# compressor.net
KiCad netlist of a schematic drawn in EAGLE
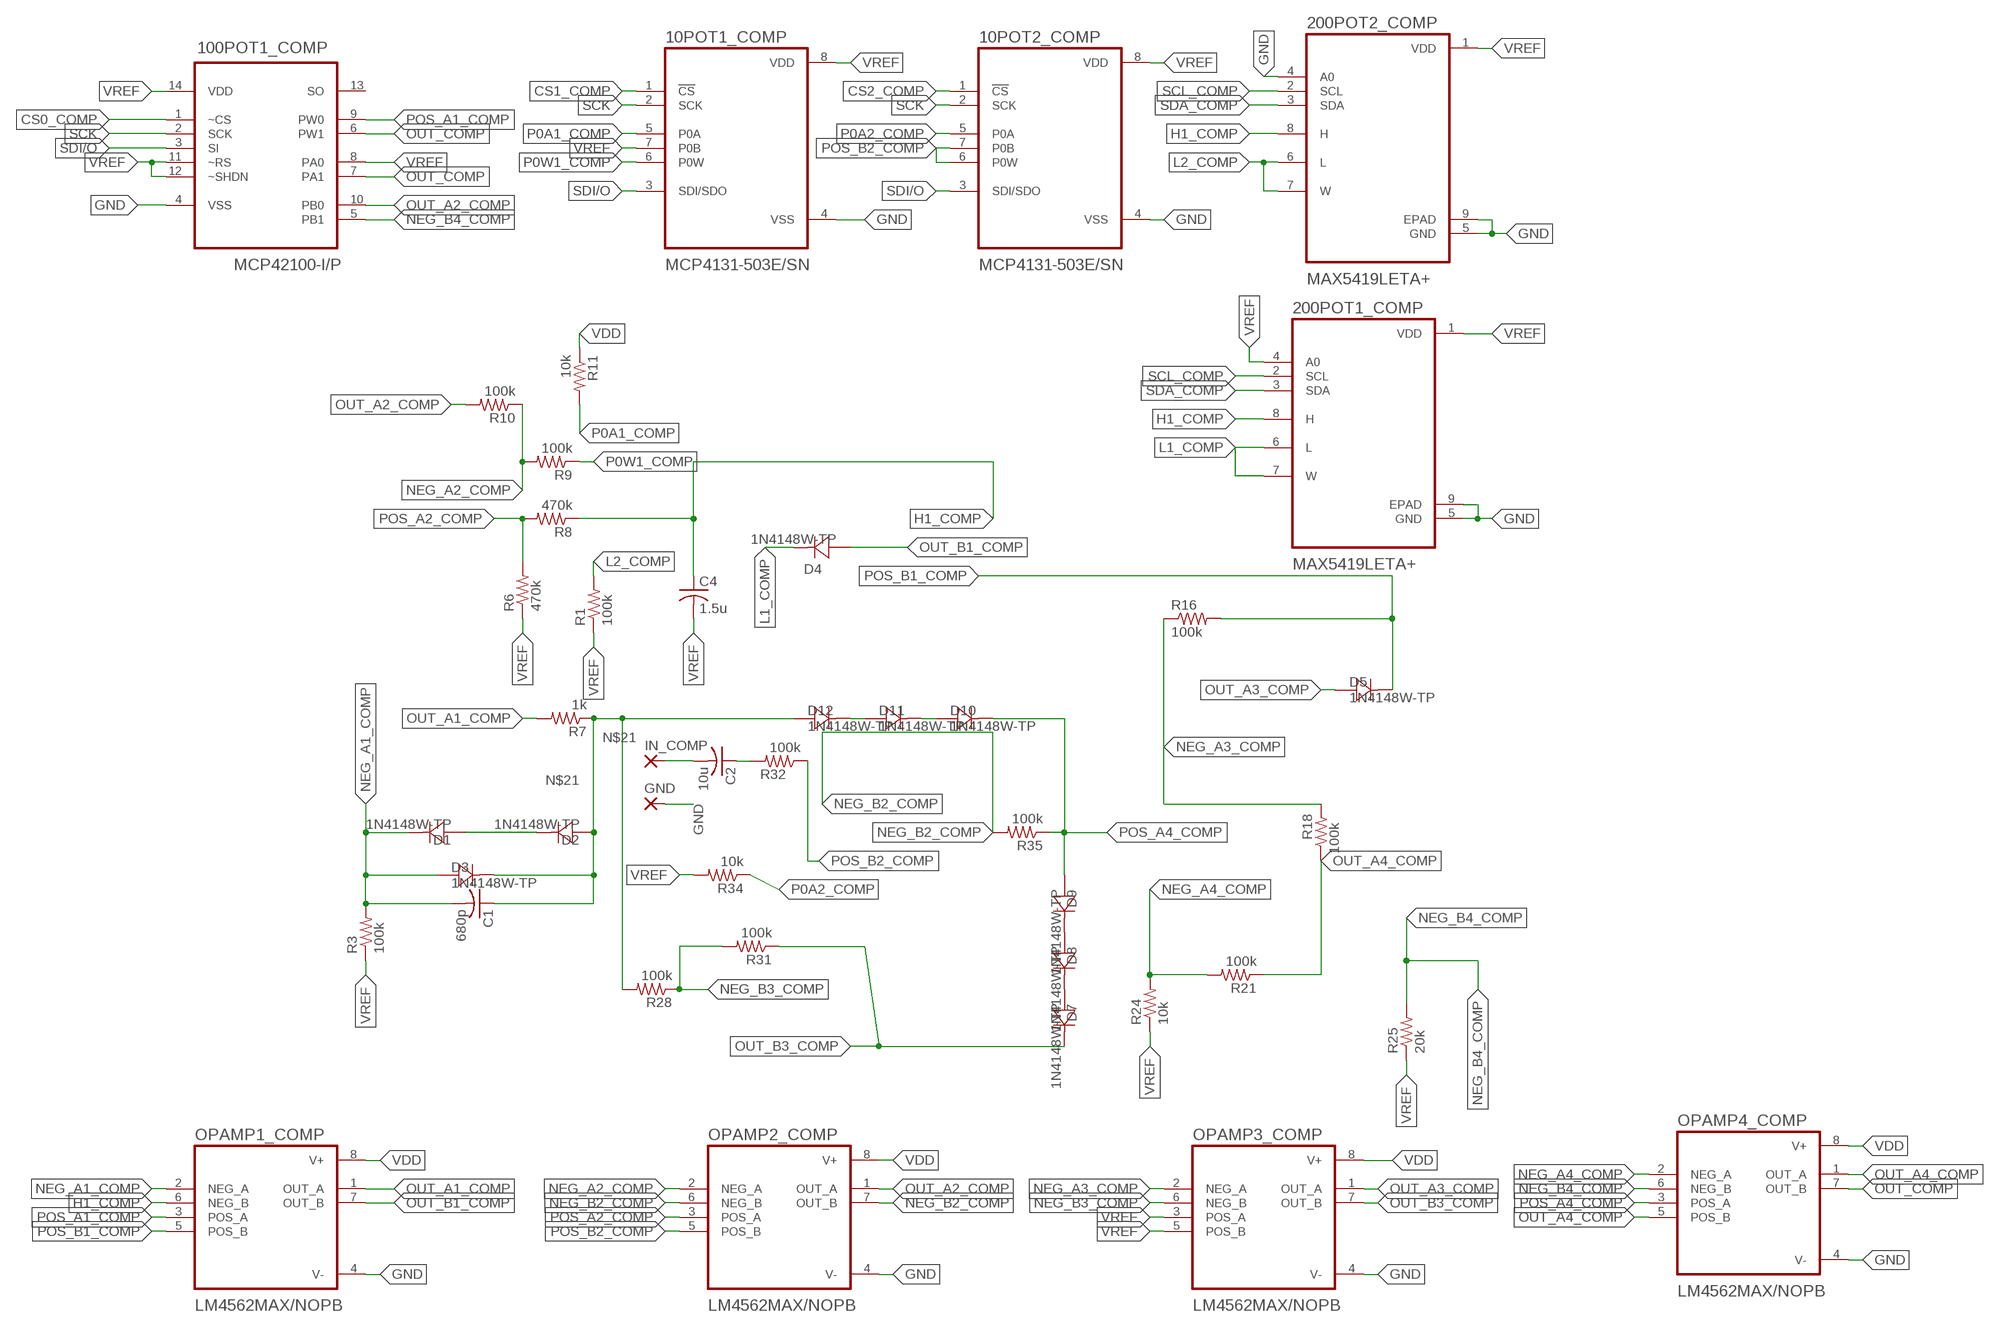
[diagram p0: schematic, sheet 1]

(export (version "E")
  (design (tool "Eeschema 10.0.6"))
  (components
    (comp (ref "10POT1_COMP")
      (value "MCP4131-503E/SN")
      (footprint "eagle-import:SOIC127P599X175-8N")
      (fields (field (name "MF") "Microchip"))
      (libsource (lib "eagle-import") (part "MCP4131-503E/SN"))
    )
    (comp (ref "10POT2_COMP")
      (value "MCP4131-503E/SN")
      (footprint "eagle-import:SOIC127P599X175-8N")
      (fields (field (name "MF") "Microchip"))
      (libsource (lib "eagle-import") (part "MCP4131-503E/SN"))
    )
    (comp (ref "100POT1_COMP")
      (value "MCP42100-I/P")
      (footprint "eagle-import:DIP254P762X432-14")
      (fields (field (name "MF") "Microchip"))
      (libsource (lib "eagle-import") (part "MCP42100-I/P"))
    )
    (comp (ref "200POT1_COMP")
      (value "MAX5419LETA+")
      (footprint "eagle-import:SON65P300X300X80-9N")
      (fields (field (name "MF") "Analog Devices"))
      (libsource (lib "eagle-import") (part "MAX5419LETA+"))
    )
    (comp (ref "200POT2_COMP")
      (value "MAX5419LETA+")
      (footprint "eagle-import:SON65P300X300X80-9N")
      (fields (field (name "MF") "Analog Devices"))
      (libsource (lib "eagle-import") (part "MAX5419LETA+"))
    )
    (comp (ref "C1")
      (value "680p")
      (footprint "eagle-import:C0402")
      (libsource (lib "eagle-import") (part "C-USC0402"))
    )
    (comp (ref "C2")
      (value "10u")
      (footprint "eagle-import:C0402")
      (libsource (lib "eagle-import") (part "C-USC0402"))
    )
    (comp (ref "C4")
      (value "1.5u")
      (footprint "eagle-import:C0402")
      (libsource (lib "eagle-import") (part "C-USC0402"))
    )
    (comp (ref "D1")
      (value "1N4148W-TP")
      (footprint "eagle-import:SOD123")
      (fields (field (name "MF") "Micro Commercial"))
      (libsource (lib "eagle-import") (part "1N4148W-TP"))
    )
    (comp (ref "D2")
      (value "1N4148W-TP")
      (footprint "eagle-import:SOD123")
      (fields (field (name "MF") "Micro Commercial"))
      (libsource (lib "eagle-import") (part "1N4148W-TP"))
    )
    (comp (ref "D3")
      (value "1N4148W-TP")
      (footprint "eagle-import:SOD123")
      (fields (field (name "MF") "Micro Commercial"))
      (libsource (lib "eagle-import") (part "1N4148W-TP"))
    )
    (comp (ref "D4")
      (value "1N4148W-TP")
      (footprint "eagle-import:SOD123")
      (fields (field (name "MF") "Micro Commercial"))
      (libsource (lib "eagle-import") (part "1N4148W-TP"))
    )
    (comp (ref "D5")
      (value "1N4148W-TP")
      (footprint "eagle-import:SOD123")
      (fields (field (name "MF") "Micro Commercial"))
      (libsource (lib "eagle-import") (part "1N4148W-TP"))
    )
    (comp (ref "D7")
      (value "1N4148W-TP")
      (footprint "eagle-import:SOD123")
      (fields (field (name "MF") "Micro Commercial"))
      (libsource (lib "eagle-import") (part "1N4148W-TP"))
    )
    (comp (ref "D8")
      (value "1N4148W-TP")
      (footprint "eagle-import:SOD123")
      (fields (field (name "MF") "Micro Commercial"))
      (libsource (lib "eagle-import") (part "1N4148W-TP"))
    )
    (comp (ref "D9")
      (value "1N4148W-TP")
      (footprint "eagle-import:SOD123")
      (fields (field (name "MF") "Micro Commercial"))
      (libsource (lib "eagle-import") (part "1N4148W-TP"))
    )
    (comp (ref "D10")
      (value "1N4148W-TP")
      (footprint "eagle-import:SOD123")
      (fields (field (name "MF") "Micro Commercial"))
      (libsource (lib "eagle-import") (part "1N4148W-TP"))
    )
    (comp (ref "D11")
      (value "1N4148W-TP")
      (footprint "eagle-import:SOD123")
      (fields (field (name "MF") "Micro Commercial"))
      (libsource (lib "eagle-import") (part "1N4148W-TP"))
    )
    (comp (ref "D12")
      (value "1N4148W-TP")
      (footprint "eagle-import:SOD123")
      (fields (field (name "MF") "Micro Commercial"))
      (libsource (lib "eagle-import") (part "1N4148W-TP"))
    )
    (comp (ref "GND")
      (value "SMD5")
      (footprint "eagle-import:SMD2,54-5,08")
      (libsource (lib "eagle-import") (part "SMD5"))
    )
    (comp (ref "IN_COMP")
      (value "SMD5")
      (footprint "eagle-import:SMD2,54-5,08")
      (libsource (lib "eagle-import") (part "SMD5"))
    )
    (comp (ref "OPAMP1_COMP")
      (value "LM4562MAX/NOPB")
      (footprint "eagle-import:SOIC127P599X175-8N")
      (fields (field (name "MF") "Texas Instruments"))
      (libsource (lib "eagle-import") (part "LM4562MAX/NOPB"))
    )
    (comp (ref "OPAMP2_COMP")
      (value "LM4562MAX/NOPB")
      (footprint "eagle-import:SOIC127P599X175-8N")
      (fields (field (name "MF") "Texas Instruments"))
      (libsource (lib "eagle-import") (part "LM4562MAX/NOPB"))
    )
    (comp (ref "OPAMP3_COMP")
      (value "LM4562MAX/NOPB")
      (footprint "eagle-import:SOIC127P599X175-8N")
      (fields (field (name "MF") "Texas Instruments"))
      (libsource (lib "eagle-import") (part "LM4562MAX/NOPB"))
    )
    (comp (ref "OPAMP4_COMP")
      (value "LM4562MAX/NOPB")
      (footprint "eagle-import:SOIC127P599X175-8N")
      (fields (field (name "MF") "Texas Instruments"))
      (libsource (lib "eagle-import") (part "LM4562MAX/NOPB"))
    )
    (comp (ref "R1")
      (value "100k")
      (footprint "eagle-import:R0402")
      (libsource (lib "eagle-import") (part "R-US_R0402"))
    )
    (comp (ref "R3")
      (value "100k")
      (footprint "eagle-import:R0402")
      (libsource (lib "eagle-import") (part "R-US_R0402"))
    )
    (comp (ref "R6")
      (value "470k")
      (footprint "eagle-import:R0402")
      (libsource (lib "eagle-import") (part "R-US_R0402"))
    )
    (comp (ref "R7")
      (value "1k")
      (footprint "eagle-import:R0402")
      (libsource (lib "eagle-import") (part "R-US_R0402"))
    )
    (comp (ref "R8")
      (value "470k")
      (footprint "eagle-import:R0402")
      (libsource (lib "eagle-import") (part "R-US_R0402"))
    )
    (comp (ref "R9")
      (value "100k")
      (footprint "eagle-import:R0402")
      (libsource (lib "eagle-import") (part "R-US_R0402"))
    )
    (comp (ref "R10")
      (value "100k")
      (footprint "eagle-import:R0402")
      (libsource (lib "eagle-import") (part "R-US_R0402"))
    )
    (comp (ref "R11")
      (value "10k")
      (footprint "eagle-import:R0402")
      (libsource (lib "eagle-import") (part "R-US_R0402"))
    )
    (comp (ref "R16")
      (value "100k")
      (footprint "eagle-import:R0402")
      (libsource (lib "eagle-import") (part "R-US_R0402"))
    )
    (comp (ref "R18")
      (value "100k")
      (footprint "eagle-import:R0402")
      (libsource (lib "eagle-import") (part "R-US_R0402"))
    )
    (comp (ref "R21")
      (value "100k")
      (footprint "eagle-import:R0402")
      (libsource (lib "eagle-import") (part "R-US_R0402"))
    )
    (comp (ref "R24")
      (value "10k")
      (footprint "eagle-import:R0402")
      (libsource (lib "eagle-import") (part "R-US_R0402"))
    )
    (comp (ref "R25")
      (value "20k")
      (footprint "eagle-import:R0402")
      (libsource (lib "eagle-import") (part "R-US_R0402"))
    )
    (comp (ref "R28")
      (value "100k")
      (footprint "eagle-import:R0402")
      (libsource (lib "eagle-import") (part "R-US_R0402"))
    )
    (comp (ref "R31")
      (value "100k")
      (footprint "eagle-import:R0402")
      (libsource (lib "eagle-import") (part "R-US_R0402"))
    )
    (comp (ref "R32")
      (value "100k")
      (footprint "eagle-import:R0402")
      (libsource (lib "eagle-import") (part "R-US_R0402"))
    )
    (comp (ref "R34")
      (value "10k")
      (footprint "eagle-import:R0402")
      (libsource (lib "eagle-import") (part "R-US_R0402"))
    )
    (comp (ref "R35")
      (value "100k")
      (footprint "eagle-import:R0402")
      (libsource (lib "eagle-import") (part "R-US_R0402"))
    )
  )
  (nets
    (net (code "1") (name "/N$21") (class "Default")
      (node (ref "C1") (pin "1") (pinfunction "1_1") (pintype "passive"))
      (node (ref "D12") (pin "A") (pinfunction "A_A") (pintype "passive"))
      (node (ref "D2") (pin "A") (pinfunction "A_A") (pintype "passive"))
      (node (ref "D3") (pin "C") (pinfunction "C_C") (pintype "passive"))
      (node (ref "R28") (pin "2") (pinfunction "2_2") (pintype "passive"))
      (node (ref "R7") (pin "1") (pinfunction "1_1") (pintype "passive"))
    )
    (net (code "2") (name "CS0_COMP") (class "Default")
      (node (ref "100POT1_COMP") (pin "1") (pinfunction "~{CS}_1") (pintype "input"))
    )
    (net (code "3") (name "CS1_COMP") (class "Default")
      (node (ref "10POT1_COMP") (pin "1") (pinfunction "~{CS}_1") (pintype "input"))
    )
    (net (code "4") (name "CS2_COMP") (class "Default")
      (node (ref "10POT2_COMP") (pin "1") (pinfunction "~{CS}_1") (pintype "input"))
    )
    (net (code "5") (name "GND") (class "Default")
      (node (ref "100POT1_COMP") (pin "4") (pinfunction "VSS_4") (pintype "passive"))
      (node (ref "10POT1_COMP") (pin "4") (pinfunction "VSS_4") (pintype "power_in"))
      (node (ref "10POT2_COMP") (pin "4") (pinfunction "VSS_4") (pintype "power_in"))
      (node (ref "200POT1_COMP") (pin "5") (pinfunction "GND_5") (pintype "power_in"))
      (node (ref "200POT1_COMP") (pin "9") (pinfunction "EPAD_9") (pintype "power_in"))
      (node (ref "200POT2_COMP") (pin "4") (pinfunction "A0_4") (pintype "input"))
      (node (ref "200POT2_COMP") (pin "5") (pinfunction "GND_5") (pintype "power_in"))
      (node (ref "200POT2_COMP") (pin "9") (pinfunction "EPAD_9") (pintype "power_in"))
      (node (ref "GND") (pin "1") (pinfunction "P_1") (pintype "passive"))
      (node (ref "OPAMP1_COMP") (pin "4") (pinfunction "V-_4") (pintype "power_in"))
      (node (ref "OPAMP2_COMP") (pin "4") (pinfunction "V-_4") (pintype "power_in"))
      (node (ref "OPAMP3_COMP") (pin "4") (pinfunction "V-_4") (pintype "power_in"))
      (node (ref "OPAMP4_COMP") (pin "4") (pinfunction "V-_4") (pintype "power_in"))
    )
    (net (code "6") (name "H1_COMP") (class "Default")
      (node (ref "200POT1_COMP") (pin "8") (pinfunction "H_8") (pintype "bidirectional"))
      (node (ref "200POT2_COMP") (pin "8") (pinfunction "H_8") (pintype "bidirectional"))
      (node (ref "C4") (pin "1") (pinfunction "1_1") (pintype "passive"))
      (node (ref "OPAMP1_COMP") (pin "6") (pinfunction "NEG_B_6") (pintype "input"))
      (node (ref "R8") (pin "1") (pinfunction "1_1") (pintype "passive"))
    )
    (net (code "7") (name "L1_COMP") (class "Default")
      (node (ref "200POT1_COMP") (pin "6") (pinfunction "L_6") (pintype "bidirectional"))
      (node (ref "200POT1_COMP") (pin "7") (pinfunction "W_7") (pintype "bidirectional"))
      (node (ref "D4") (pin "C") (pinfunction "C_C") (pintype "passive"))
    )
    (net (code "8") (name "L2_COMP") (class "Default")
      (node (ref "200POT2_COMP") (pin "6") (pinfunction "L_6") (pintype "bidirectional"))
      (node (ref "200POT2_COMP") (pin "7") (pinfunction "W_7") (pintype "bidirectional"))
      (node (ref "R1") (pin "2") (pinfunction "2_2") (pintype "passive"))
    )
    (net (code "9") (name "NEG_A1_COMP") (class "Default")
      (node (ref "C1") (pin "2") (pinfunction "2_2") (pintype "passive"))
      (node (ref "D1") (pin "C") (pinfunction "C_C") (pintype "passive"))
      (node (ref "D3") (pin "A") (pinfunction "A_A") (pintype "passive"))
      (node (ref "OPAMP1_COMP") (pin "2") (pinfunction "NEG_A_2") (pintype "input"))
      (node (ref "R3") (pin "2") (pinfunction "2_2") (pintype "passive"))
    )
    (net (code "10") (name "NEG_A2_COMP") (class "Default")
      (node (ref "OPAMP2_COMP") (pin "2") (pinfunction "NEG_A_2") (pintype "input"))
      (node (ref "R10") (pin "1") (pinfunction "1_1") (pintype "passive"))
      (node (ref "R9") (pin "2") (pinfunction "2_2") (pintype "passive"))
    )
    (net (code "11") (name "NEG_A3_COMP") (class "Default")
      (node (ref "OPAMP3_COMP") (pin "2") (pinfunction "NEG_A_2") (pintype "input"))
      (node (ref "R16") (pin "1") (pinfunction "1_1") (pintype "passive"))
      (node (ref "R18") (pin "2") (pinfunction "2_2") (pintype "passive"))
    )
    (net (code "12") (name "NEG_A4_COMP") (class "Default")
      (node (ref "OPAMP4_COMP") (pin "2") (pinfunction "NEG_A_2") (pintype "input"))
      (node (ref "R21") (pin "2") (pinfunction "2_2") (pintype "passive"))
      (node (ref "R24") (pin "2") (pinfunction "2_2") (pintype "passive"))
    )
    (net (code "13") (name "NEG_B2_COMP") (class "Default")
      (node (ref "OPAMP2_COMP") (pin "6") (pinfunction "NEG_B_6") (pintype "input"))
      (node (ref "OPAMP2_COMP") (pin "7") (pinfunction "OUT_B_7") (pintype "output"))
      (node (ref "R35") (pin "2") (pinfunction "2_2") (pintype "passive"))
    )
    (net (code "14") (name "NEG_B3_COMP") (class "Default")
      (node (ref "OPAMP3_COMP") (pin "6") (pinfunction "NEG_B_6") (pintype "input"))
      (node (ref "R28") (pin "1") (pinfunction "1_1") (pintype "passive"))
      (node (ref "R31") (pin "2") (pinfunction "2_2") (pintype "passive"))
    )
    (net (code "15") (name "NEG_B4_COMP") (class "Default")
      (node (ref "100POT1_COMP") (pin "5") (pinfunction "PB1_5") (pintype "passive"))
      (node (ref "OPAMP4_COMP") (pin "6") (pinfunction "NEG_B_6") (pintype "input"))
      (node (ref "R25") (pin "2") (pinfunction "2_2") (pintype "passive"))
    )
    (net (code "16") (name "Net-(C2-Pad1)") (class "Default")
      (node (ref "C2") (pin "1") (pinfunction "1_1") (pintype "passive"))
      (node (ref "R32") (pin "2") (pinfunction "2_2") (pintype "passive"))
    )
    (net (code "17") (name "Net-(D1-PadA)") (class "Default")
      (node (ref "D1") (pin "A") (pinfunction "A_A") (pintype "passive"))
      (node (ref "D2") (pin "C") (pinfunction "C_C") (pintype "passive"))
    )
    (net (code "18") (name "Net-(D7-PadA)") (class "Default")
      (node (ref "D7") (pin "A") (pinfunction "A_A") (pintype "passive"))
      (node (ref "D8") (pin "C") (pinfunction "C_C") (pintype "passive"))
    )
    (net (code "19") (name "Net-(D8-PadA)") (class "Default")
      (node (ref "D8") (pin "A") (pinfunction "A_A") (pintype "passive"))
      (node (ref "D9") (pin "C") (pinfunction "C_C") (pintype "passive"))
    )
    (net (code "20") (name "Net-(D10-PadA)") (class "Default")
      (node (ref "D10") (pin "A") (pinfunction "A_A") (pintype "passive"))
      (node (ref "D11") (pin "C") (pinfunction "C_C") (pintype "passive"))
    )
    (net (code "21") (name "Net-(D11-PadA)") (class "Default")
      (node (ref "D11") (pin "A") (pinfunction "A_A") (pintype "passive"))
      (node (ref "D12") (pin "C") (pinfunction "C_C") (pintype "passive"))
    )
    (net (code "22") (name "Net-(IN_COMP-P)") (class "Default")
      (node (ref "C2") (pin "2") (pinfunction "2_2") (pintype "passive"))
      (node (ref "IN_COMP") (pin "1") (pinfunction "P_1") (pintype "passive"))
    )
    (net (code "23") (name "OUT_A1_COMP") (class "Default")
      (node (ref "OPAMP1_COMP") (pin "1") (pinfunction "OUT_A_1") (pintype "output"))
      (node (ref "R7") (pin "2") (pinfunction "2_2") (pintype "passive"))
    )
    (net (code "24") (name "OUT_A2_COMP") (class "Default")
      (node (ref "100POT1_COMP") (pin "10") (pinfunction "PB0_10") (pintype "passive"))
      (node (ref "OPAMP2_COMP") (pin "1") (pinfunction "OUT_A_1") (pintype "output"))
      (node (ref "R10") (pin "2") (pinfunction "2_2") (pintype "passive"))
    )
    (net (code "25") (name "OUT_A3_COMP") (class "Default")
      (node (ref "D5") (pin "A") (pinfunction "A_A") (pintype "passive"))
      (node (ref "OPAMP3_COMP") (pin "1") (pinfunction "OUT_A_1") (pintype "output"))
    )
    (net (code "26") (name "OUT_A4_COMP") (class "Default")
      (node (ref "OPAMP4_COMP") (pin "1") (pinfunction "OUT_A_1") (pintype "output"))
      (node (ref "OPAMP4_COMP") (pin "5") (pinfunction "POS_B_5") (pintype "input"))
      (node (ref "R18") (pin "1") (pinfunction "1_1") (pintype "passive"))
      (node (ref "R21") (pin "1") (pinfunction "1_1") (pintype "passive"))
    )
    (net (code "27") (name "OUT_B1_COMP") (class "Default")
      (node (ref "D4") (pin "A") (pinfunction "A_A") (pintype "passive"))
      (node (ref "OPAMP1_COMP") (pin "7") (pinfunction "OUT_B_7") (pintype "output"))
    )
    (net (code "28") (name "OUT_B3_COMP") (class "Default")
      (node (ref "D7") (pin "C") (pinfunction "C_C") (pintype "passive"))
      (node (ref "OPAMP3_COMP") (pin "7") (pinfunction "OUT_B_7") (pintype "output"))
      (node (ref "R31") (pin "1") (pinfunction "1_1") (pintype "passive"))
    )
    (net (code "29") (name "OUT_COMP") (class "Default")
      (node (ref "100POT1_COMP") (pin "6") (pinfunction "PW1_6") (pintype "passive"))
      (node (ref "100POT1_COMP") (pin "7") (pinfunction "PA1_7") (pintype "passive"))
      (node (ref "OPAMP4_COMP") (pin "7") (pinfunction "OUT_B_7") (pintype "output"))
    )
    (net (code "30") (name "P0A1_COMP") (class "Default")
      (node (ref "10POT1_COMP") (pin "5") (pinfunction "P0A_5") (pintype "bidirectional"))
      (node (ref "R11") (pin "2") (pinfunction "2_2") (pintype "passive"))
    )
    (net (code "31") (name "P0A2_COMP") (class "Default")
      (node (ref "10POT2_COMP") (pin "5") (pinfunction "P0A_5") (pintype "bidirectional"))
      (node (ref "R34") (pin "1") (pinfunction "1_1") (pintype "passive"))
    )
    (net (code "32") (name "P0W1_COMP") (class "Default")
      (node (ref "10POT1_COMP") (pin "6") (pinfunction "P0W_6") (pintype "bidirectional"))
      (node (ref "R9") (pin "1") (pinfunction "1_1") (pintype "passive"))
    )
    (net (code "33") (name "POS_A1_COMP") (class "Default")
      (node (ref "100POT1_COMP") (pin "9") (pinfunction "PW0_9") (pintype "passive"))
      (node (ref "OPAMP1_COMP") (pin "3") (pinfunction "POS_A_3") (pintype "input"))
    )
    (net (code "34") (name "POS_A2_COMP") (class "Default")
      (node (ref "OPAMP2_COMP") (pin "3") (pinfunction "POS_A_3") (pintype "input"))
      (node (ref "R6") (pin "2") (pinfunction "2_2") (pintype "passive"))
      (node (ref "R8") (pin "2") (pinfunction "2_2") (pintype "passive"))
    )
    (net (code "35") (name "POS_A4_COMP") (class "Default")
      (node (ref "D10") (pin "C") (pinfunction "C_C") (pintype "passive"))
      (node (ref "D9") (pin "A") (pinfunction "A_A") (pintype "passive"))
      (node (ref "OPAMP4_COMP") (pin "3") (pinfunction "POS_A_3") (pintype "input"))
      (node (ref "R35") (pin "1") (pinfunction "1_1") (pintype "passive"))
    )
    (net (code "36") (name "POS_B1_COMP") (class "Default")
      (node (ref "D5") (pin "C") (pinfunction "C_C") (pintype "passive"))
      (node (ref "OPAMP1_COMP") (pin "5") (pinfunction "POS_B_5") (pintype "input"))
      (node (ref "R16") (pin "2") (pinfunction "2_2") (pintype "passive"))
    )
    (net (code "37") (name "POS_B2_COMP") (class "Default")
      (node (ref "10POT2_COMP") (pin "6") (pinfunction "P0W_6") (pintype "bidirectional"))
      (node (ref "10POT2_COMP") (pin "7") (pinfunction "P0B_7") (pintype "bidirectional"))
      (node (ref "OPAMP2_COMP") (pin "5") (pinfunction "POS_B_5") (pintype "input"))
      (node (ref "R32") (pin "1") (pinfunction "1_1") (pintype "passive"))
    )
    (net (code "38") (name "SCK") (class "Default")
      (node (ref "100POT1_COMP") (pin "2") (pinfunction "SCK_2") (pintype "input"))
      (node (ref "10POT1_COMP") (pin "2") (pinfunction "SCK_2") (pintype "input"))
      (node (ref "10POT2_COMP") (pin "2") (pinfunction "SCK_2") (pintype "input"))
    )
    (net (code "39") (name "SCL_COMP") (class "Default")
      (node (ref "200POT1_COMP") (pin "2") (pinfunction "SCL_2") (pintype "input"))
      (node (ref "200POT2_COMP") (pin "2") (pinfunction "SCL_2") (pintype "input"))
    )
    (net (code "40") (name "SDA_COMP") (class "Default")
      (node (ref "200POT1_COMP") (pin "3") (pinfunction "SDA_3") (pintype "input"))
      (node (ref "200POT2_COMP") (pin "3") (pinfunction "SDA_3") (pintype "input"))
    )
    (net (code "41") (name "SDI{slash}O") (class "Default")
      (node (ref "100POT1_COMP") (pin "3") (pinfunction "SI_3") (pintype "input"))
      (node (ref "10POT1_COMP") (pin "3") (pinfunction "SDI/SDO_3") (pintype "bidirectional"))
      (node (ref "10POT2_COMP") (pin "3") (pinfunction "SDI/SDO_3") (pintype "bidirectional"))
    )
    (net (code "42") (name "VDD") (class "Default")
      (node (ref "OPAMP1_COMP") (pin "8") (pinfunction "V+_8") (pintype "power_in"))
      (node (ref "OPAMP2_COMP") (pin "8") (pinfunction "V+_8") (pintype "power_in"))
      (node (ref "OPAMP3_COMP") (pin "8") (pinfunction "V+_8") (pintype "power_in"))
      (node (ref "OPAMP4_COMP") (pin "8") (pinfunction "V+_8") (pintype "power_in"))
      (node (ref "R11") (pin "1") (pinfunction "1_1") (pintype "passive"))
    )
    (net (code "43") (name "VREF") (class "Default")
      (node (ref "100POT1_COMP") (pin "11") (pinfunction "~{RS}_11") (pintype "input"))
      (node (ref "100POT1_COMP") (pin "12") (pinfunction "~{SHDN}_12") (pintype "input"))
      (node (ref "100POT1_COMP") (pin "14") (pinfunction "VDD_14") (pintype "power_in"))
      (node (ref "100POT1_COMP") (pin "8") (pinfunction "PA0_8") (pintype "passive"))
      (node (ref "10POT1_COMP") (pin "7") (pinfunction "P0B_7") (pintype "bidirectional"))
      (node (ref "10POT1_COMP") (pin "8") (pinfunction "VDD_8") (pintype "power_in"))
      (node (ref "10POT2_COMP") (pin "8") (pinfunction "VDD_8") (pintype "power_in"))
      (node (ref "200POT1_COMP") (pin "1") (pinfunction "VDD_1") (pintype "power_in"))
      (node (ref "200POT1_COMP") (pin "4") (pinfunction "A0_4") (pintype "input"))
      (node (ref "200POT2_COMP") (pin "1") (pinfunction "VDD_1") (pintype "power_in"))
      (node (ref "C4") (pin "2") (pinfunction "2_2") (pintype "passive"))
      (node (ref "OPAMP3_COMP") (pin "3") (pinfunction "POS_A_3") (pintype "input"))
      (node (ref "OPAMP3_COMP") (pin "5") (pinfunction "POS_B_5") (pintype "input"))
      (node (ref "R1") (pin "1") (pinfunction "1_1") (pintype "passive"))
      (node (ref "R24") (pin "1") (pinfunction "1_1") (pintype "passive"))
      (node (ref "R25") (pin "1") (pinfunction "1_1") (pintype "passive"))
      (node (ref "R3") (pin "1") (pinfunction "1_1") (pintype "passive"))
      (node (ref "R34") (pin "2") (pinfunction "2_2") (pintype "passive"))
      (node (ref "R6") (pin "1") (pinfunction "1_1") (pintype "passive"))
    )
    (net (code "44") (name "unconnected-(100POT1_COMP-SO-Pad13)") (class "Default")
      (node (ref "100POT1_COMP") (pin "13") (pinfunction "SO_13") (pintype "output"))
    )
  )
)
